# Supply-STM32.net
KiCad netlist of a schematic drawn in Altium Designer
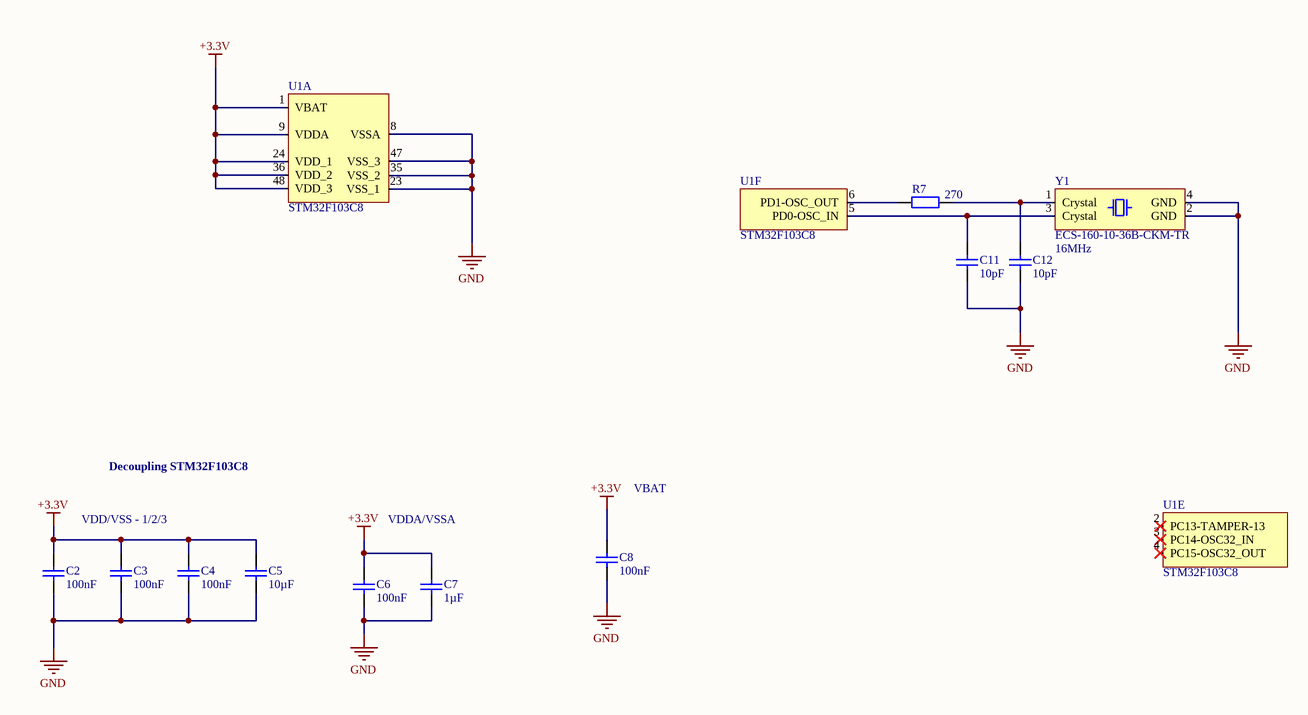
[diagram p0: Supply-STM32.SchDoc]

(export (version "E")
  (design (tool "Eeschema 10.0.6"))
  (components
    (comp (ref "C2")
      (value "100nF")
      (footprint "CAP_0603")
      (fields (field (name "Comment") "CAP"))
      (libsource (lib "Passive") (part "CAP"))
    )
    (comp (ref "C3")
      (value "100nF")
      (footprint "CAP_0603")
      (fields (field (name "Comment") "CAP"))
      (libsource (lib "Passive") (part "CAP"))
    )
    (comp (ref "C4")
      (value "100nF")
      (footprint "CAP_0603")
      (fields (field (name "Comment") "CAP"))
      (libsource (lib "Passive") (part "CAP"))
    )
    (comp (ref "C5")
      (value "10µF")
      (footprint "CAP_0603")
      (fields (field (name "Comment") "CAP"))
      (libsource (lib "Passive") (part "CAP"))
    )
    (comp (ref "C6")
      (value "100nF")
      (footprint "CAP_0603")
      (fields (field (name "Comment") "CAP"))
      (libsource (lib "Passive") (part "CAP"))
    )
    (comp (ref "C7")
      (value "1µF")
      (footprint "CAP_0603")
      (fields (field (name "Comment") "CAP"))
      (libsource (lib "Passive") (part "CAP"))
    )
    (comp (ref "C8")
      (value "100nF")
      (footprint "CAP_0603")
      (fields (field (name "Comment") "CAP"))
      (libsource (lib "Passive") (part "CAP"))
    )
    (comp (ref "C11")
      (value "10pF")
      (footprint "CAP_0603")
      (fields (field (name "Comment") "CAP"))
      (libsource (lib "Passive") (part "CAP"))
    )
    (comp (ref "C12")
      (value "10pF")
      (footprint "CAP_0603")
      (fields (field (name "Comment") "CAP"))
      (libsource (lib "Passive") (part "CAP"))
    )
    (comp (ref "R7")
      (value "270")
      (footprint "RES_0603")
      (fields (field (name "Comment") "RES"))
      (libsource (lib "Passive") (part "RES"))
    )
    (comp (ref "U1")
      (value "STM32F103C8")
      (footprint "LQFP48P05S97X97")
      (libsource (lib "ST") (part "STM32F103C8"))
    )
    (comp (ref "Y1")
      (value "ECS-160-10-36B-CKM-TR")
      (footprint "Crystal_16MHz")
      (fields (field (name "PARAMETER 1") "16MHz"))
      (libsource (lib "ECS") (part "ECS-160-10-36B-CKM-TR"))
    )
  )
  (nets
    (net (code "1") (name "+3.3V") (class "Default")
      (node (ref "C2") (pin "2") (pinfunction "2_2") (pintype "passive"))
      (node (ref "C3") (pin "2") (pinfunction "2_2") (pintype "passive"))
      (node (ref "C4") (pin "2") (pinfunction "2_2") (pintype "passive"))
      (node (ref "C5") (pin "2") (pinfunction "2_2") (pintype "passive"))
      (node (ref "C6") (pin "2") (pinfunction "2_2") (pintype "passive"))
      (node (ref "C7") (pin "2") (pinfunction "2_2") (pintype "passive"))
      (node (ref "C8") (pin "2") (pinfunction "2_2") (pintype "passive"))
      (node (ref "U1") (pin "1") (pinfunction "VBAT_1") (pintype "power_in"))
      (node (ref "U1") (pin "24") (pinfunction "VDD_1_24") (pintype "power_in"))
      (node (ref "U1") (pin "36") (pinfunction "VDD_2_36") (pintype "power_in"))
      (node (ref "U1") (pin "48") (pinfunction "VDD_3_48") (pintype "power_in"))
      (node (ref "U1") (pin "9") (pinfunction "VDDA_9") (pintype "power_in"))
    )
    (net (code "2") (name "GND") (class "Default")
      (node (ref "C11") (pin "1") (pinfunction "1_1") (pintype "passive"))
      (node (ref "C12") (pin "1") (pinfunction "1_1") (pintype "passive"))
      (node (ref "C2") (pin "1") (pinfunction "1_1") (pintype "passive"))
      (node (ref "C3") (pin "1") (pinfunction "1_1") (pintype "passive"))
      (node (ref "C4") (pin "1") (pinfunction "1_1") (pintype "passive"))
      (node (ref "C5") (pin "1") (pinfunction "1_1") (pintype "passive"))
      (node (ref "C6") (pin "1") (pinfunction "1_1") (pintype "passive"))
      (node (ref "C7") (pin "1") (pinfunction "1_1") (pintype "passive"))
      (node (ref "C8") (pin "1") (pinfunction "1_1") (pintype "passive"))
      (node (ref "U1") (pin "23") (pinfunction "VSS_1_23") (pintype "power_in"))
      (node (ref "U1") (pin "35") (pinfunction "VSS_2_35") (pintype "power_in"))
      (node (ref "U1") (pin "47") (pinfunction "VSS_3_47") (pintype "power_in"))
      (node (ref "U1") (pin "8") (pinfunction "VSSA_8") (pintype "power_in"))
      (node (ref "Y1") (pin "2") (pinfunction "GND_2") (pintype "power_in"))
      (node (ref "Y1") (pin "4") (pinfunction "GND_4") (pintype "power_in"))
    )
    (net (code "3") (name "Net-(C12-Pad2)") (class "Default")
      (node (ref "C12") (pin "2") (pinfunction "2_2") (pintype "passive"))
      (node (ref "R7") (pin "1") (pinfunction "1_1") (pintype "passive"))
      (node (ref "Y1") (pin "1") (pinfunction "Crystal_1") (pintype "passive"))
    )
    (net (code "4") (name "Net-(U1F-PD0-OSC_IN)") (class "Default")
      (node (ref "C11") (pin "2") (pinfunction "2_2") (pintype "passive"))
      (node (ref "U1") (pin "5") (pinfunction "PD0-OSC_IN_5") (pintype "bidirectional"))
      (node (ref "Y1") (pin "3") (pinfunction "Crystal_3") (pintype "passive"))
    )
    (net (code "5") (name "Net-(U1F-PD1-OSC_OUT)") (class "Default")
      (node (ref "R7") (pin "2") (pinfunction "2_2") (pintype "passive"))
      (node (ref "U1") (pin "6") (pinfunction "PD1-OSC_OUT_6") (pintype "bidirectional"))
    )
    (net (code "6") (name "unconnected-(U1E-PC13-TAMPER-13-Pad2)") (class "Default")
      (node (ref "U1") (pin "2") (pinfunction "PC13-TAMPER-13_2") (pintype "bidirectional+no_connect"))
    )
    (net (code "7") (name "unconnected-(U1E-PC14-OSC32_IN-Pad3)") (class "Default")
      (node (ref "U1") (pin "3") (pinfunction "PC14-OSC32_IN_3") (pintype "bidirectional+no_connect"))
    )
    (net (code "8") (name "unconnected-(U1E-PC15-OSC32_OUT-Pad4)") (class "Default")
      (node (ref "U1") (pin "4") (pinfunction "PC15-OSC32_OUT_4") (pintype "bidirectional+no_connect"))
    )
  )
)
